# STUDNA.net
KiCad netlist of a schematic drawn in EAGLE
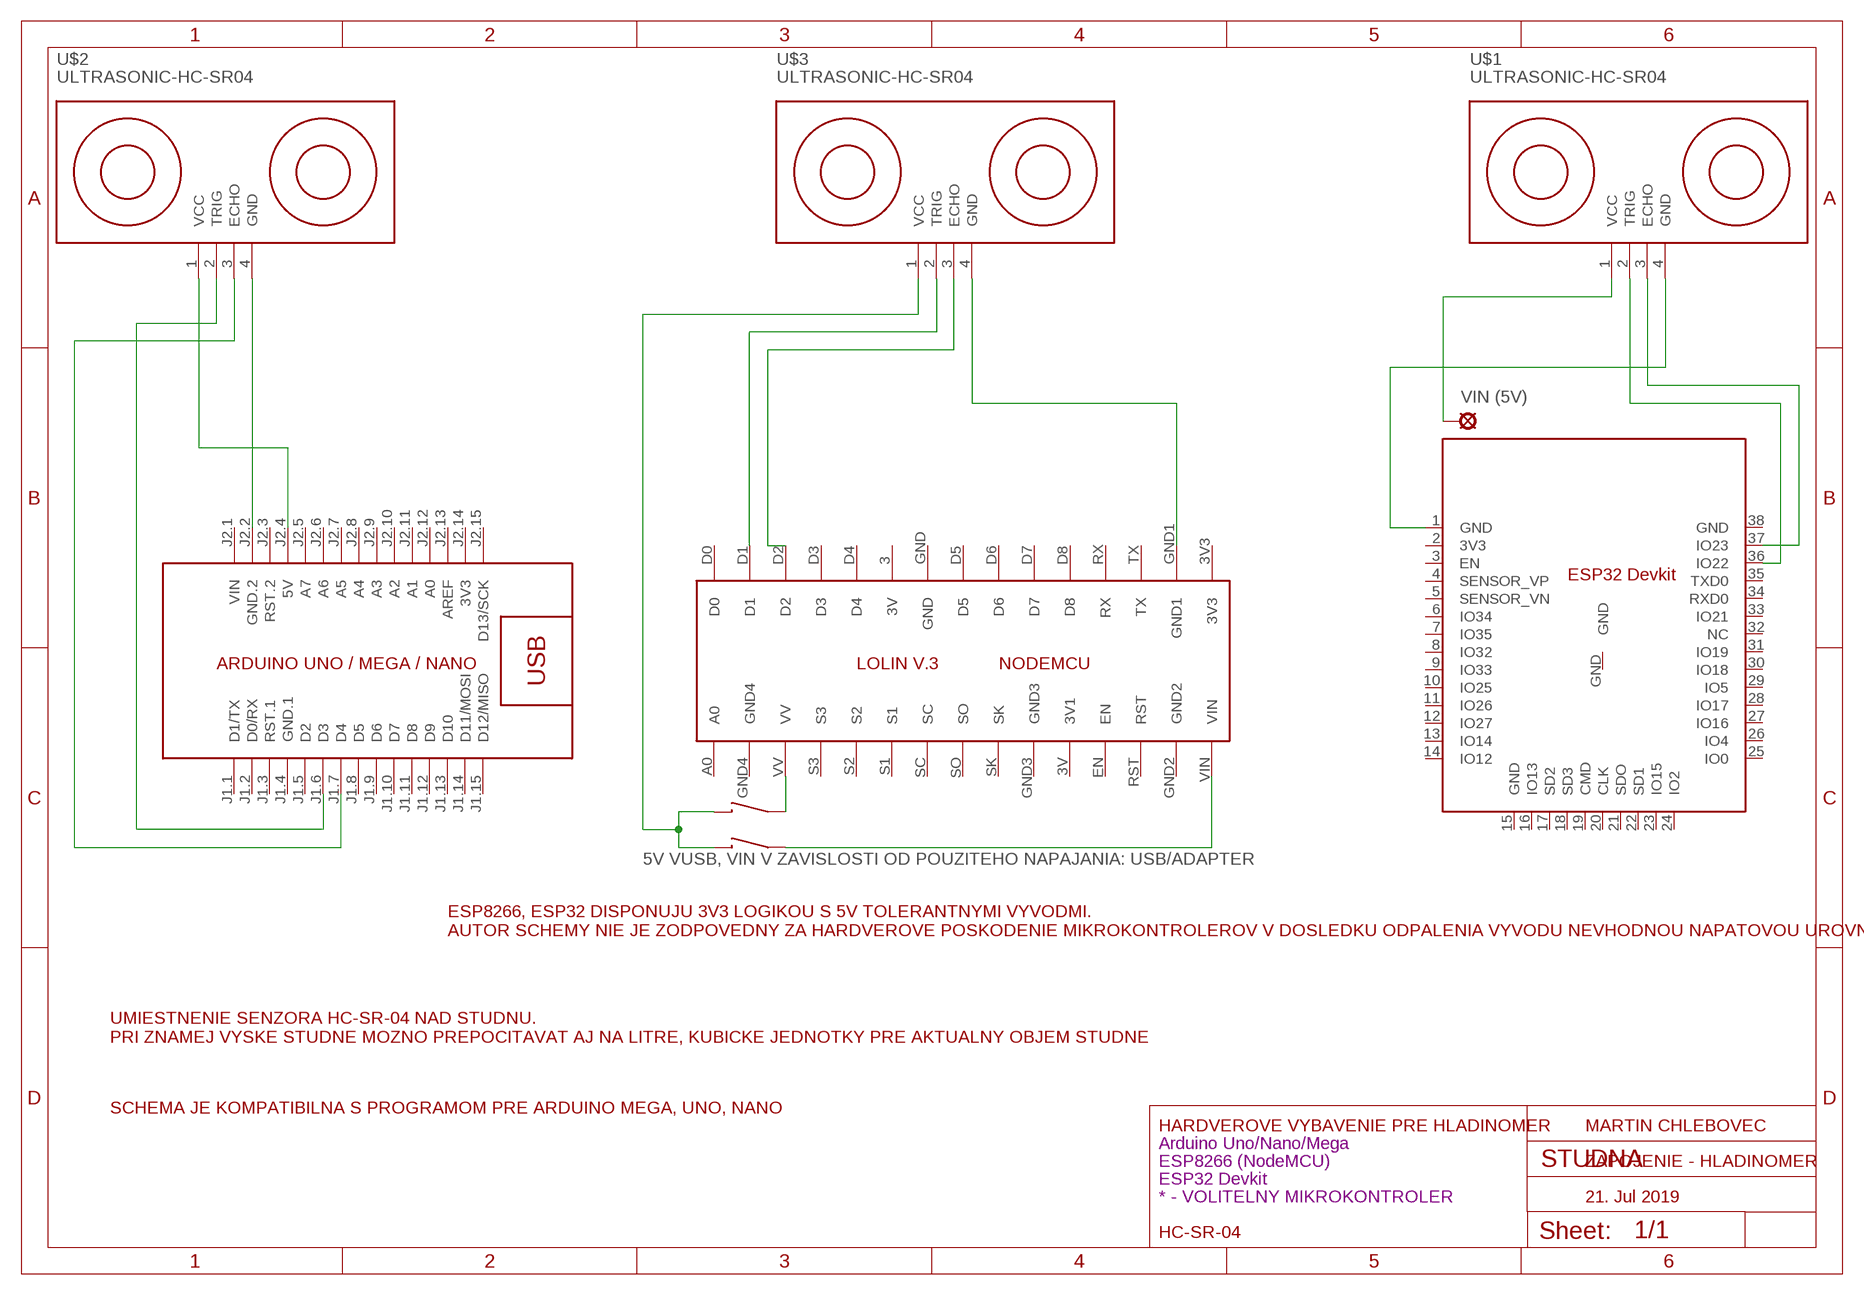
[diagram p0: schematic, sheet 1]

(export (version "E")
  (design (tool "Eeschema 10.0.6"))
  (components
    (comp (ref "A")
      (value "FINGERPAD-2B")
      (footprint "eagle-import:FINGERPAD-2B")
      (libsource (lib "eagle-import") (part "FINGERPAD-2B"))
    )
    (comp (ref "A1")
      (value "FINGERPAD-2B")
      (footprint "eagle-import:FINGERPAD-2B")
      (libsource (lib "eagle-import") (part "FINGERPAD-2B"))
    )
    (comp (ref "IC1")
      (value "LOLINV3")
      (footprint "eagle-import:LOLINV3")
      (libsource (lib "eagle-import") (part "LOLINV3"))
    )
    (comp (ref "LSP1")
      (value "MCS10B")
      (footprint "eagle-import:MCS10B")
      (libsource (lib "eagle-import") (part "MCS10B"))
    )
    (comp (ref "M1")
      (value "ARDUINO-NANO-3.0")
      (footprint "eagle-import:ARDUINO-NANO-3.0")
      (libsource (lib "eagle-import") (part "ARDUINO-NANO-3.0"))
    )
    (comp (ref "U$1")
      (value "ULTRASONIC-HC-SR04")
      (footprint "eagle-import:ULTRASONIC-HC-SR04")
      (libsource (lib "eagle-import") (part "ULTRASONIC-HC-SR04"))
    )
    (comp (ref "U$2")
      (value "ULTRASONIC-HC-SR04")
      (footprint "eagle-import:ULTRASONIC-HC-SR04")
      (libsource (lib "eagle-import") (part "ULTRASONIC-HC-SR04"))
    )
    (comp (ref "U$3")
      (value "ULTRASONIC-HC-SR04")
      (footprint "eagle-import:ULTRASONIC-HC-SR04")
      (libsource (lib "eagle-import") (part "ULTRASONIC-HC-SR04"))
    )
    (comp (ref "U1")
      (value "ESP-WROOM-32")
      (footprint "eagle-import:ESP-WROOM-32")
      (libsource (lib "eagle-import") (part "ESP-WROOM-32"))
    )
  )
  (nets
    (net (code "1") (name "/3V3") (class "Default")
      (node (ref "M1") (pin "J2.14") (pinfunction "3V3_J2.14") (pintype "power_in"))
    )
    (net (code "2") (name "/GND.1") (class "Default")
      (node (ref "M1") (pin "J1.4") (pinfunction "GND.1_J1.4") (pintype "power_in"))
    )
    (net (code "3") (name "/VIN") (class "Default")
      (node (ref "M1") (pin "J2.1") (pinfunction "VIN_J2.1") (pintype "power_in"))
    )
    (net (code "4") (name "Net-(A-Pad1)") (class "Default")
      (node (ref "A") (pin "1") (pinfunction "1_1") (pintype "passive"))
      (node (ref "IC1") (pin "VV") (pinfunction "VV_VV") (pintype "bidirectional"))
    )
    (net (code "5") (name "Net-(A1-Pad1)") (class "Default")
      (node (ref "A1") (pin "1") (pinfunction "1_1") (pintype "passive"))
      (node (ref "IC1") (pin "VIN") (pinfunction "VIN_VIN") (pintype "bidirectional"))
    )
    (net (code "6") (name "Net-(M1-5V)") (class "Default")
      (node (ref "M1") (pin "J2.4") (pinfunction "5V_J2.4") (pintype "power_in"))
      (node (ref "U$2") (pin "1") (pinfunction "VCC_1") (pintype "power_in"))
    )
    (net (code "7") (name "Net-(M1-D3)") (class "Default")
      (node (ref "M1") (pin "J1.6") (pinfunction "D3_J1.6") (pintype "bidirectional"))
      (node (ref "U$2") (pin "2") (pinfunction "TRIG_2") (pintype "input"))
    )
    (net (code "8") (name "Net-(M1-D4)") (class "Default")
      (node (ref "M1") (pin "J1.7") (pinfunction "D4_J1.7") (pintype "bidirectional"))
      (node (ref "U$2") (pin "3") (pinfunction "ECHO_3") (pintype "output"))
    )
    (net (code "9") (name "Net-(M1-GND.2)") (class "Default")
      (node (ref "M1") (pin "J2.2") (pinfunction "GND.2_J2.2") (pintype "power_in"))
      (node (ref "U$2") (pin "4") (pinfunction "GND_4") (pintype "power_in"))
    )
    (net (code "10") (name "Net-(U$1-ECHO)") (class "Default")
      (node (ref "U$1") (pin "3") (pinfunction "ECHO_3") (pintype "output"))
      (node (ref "U1") (pin "37") (pinfunction "IO23_37") (pintype "bidirectional"))
    )
    (net (code "11") (name "Net-(U$1-GND)") (class "Default")
      (node (ref "U$1") (pin "4") (pinfunction "GND_4") (pintype "power_in"))
      (node (ref "U1") (pin "1") (pinfunction "GND_1") (pintype "bidirectional"))
    )
    (net (code "12") (name "Net-(U$1-TRIG)") (class "Default")
      (node (ref "U$1") (pin "2") (pinfunction "TRIG_2") (pintype "input"))
      (node (ref "U1") (pin "36") (pinfunction "IO22_36") (pintype "bidirectional"))
    )
    (net (code "13") (name "Net-(U$1-VCC)") (class "Default")
      (node (ref "LSP1") (pin "MP") (pinfunction "MP_MP") (pintype "passive"))
      (node (ref "U$1") (pin "1") (pinfunction "VCC_1") (pintype "power_in"))
    )
    (net (code "14") (name "Net-(U$3-ECHO)") (class "Default")
      (node (ref "IC1") (pin "D2") (pinfunction "D2_D2") (pintype "bidirectional"))
      (node (ref "U$3") (pin "3") (pinfunction "ECHO_3") (pintype "output"))
    )
    (net (code "15") (name "Net-(U$3-GND)") (class "Default")
      (node (ref "IC1") (pin "GND1") (pinfunction "GND1_GND1") (pintype "bidirectional"))
      (node (ref "U$3") (pin "4") (pinfunction "GND_4") (pintype "power_in"))
    )
    (net (code "16") (name "Net-(U$3-TRIG)") (class "Default")
      (node (ref "IC1") (pin "D1") (pinfunction "D1_D1") (pintype "bidirectional"))
      (node (ref "U$3") (pin "2") (pinfunction "TRIG_2") (pintype "input"))
    )
    (net (code "17") (name "Net-(U$3-VCC)") (class "Default")
      (node (ref "A") (pin "2") (pinfunction "2_2") (pintype "passive"))
      (node (ref "A1") (pin "2") (pinfunction "2_2") (pintype "passive"))
      (node (ref "U$3") (pin "1") (pinfunction "VCC_1") (pintype "power_in"))
    )
    (net (code "18") (name "unconnected-(IC1-3V-Pad3)") (class "Default")
      (node (ref "IC1") (pin "3") (pinfunction "3V_3") (pintype "bidirectional"))
    )
    (net (code "19") (name "unconnected-(IC1-3V1-Pad3V)") (class "Default")
      (node (ref "IC1") (pin "3V") (pinfunction "3V1_3V") (pintype "bidirectional"))
    )
    (net (code "20") (name "unconnected-(IC1-Pad3V3)") (class "Default")
      (node (ref "IC1") (pin "3V3") (pinfunction "3V3_3V3") (pintype "bidirectional"))
    )
    (net (code "21") (name "unconnected-(IC1-PadA0)") (class "Default")
      (node (ref "IC1") (pin "A0") (pinfunction "A0_A0") (pintype "bidirectional"))
    )
    (net (code "22") (name "unconnected-(IC1-PadD0)") (class "Default")
      (node (ref "IC1") (pin "D0") (pinfunction "D0_D0") (pintype "bidirectional"))
    )
    (net (code "23") (name "unconnected-(IC1-PadD3)") (class "Default")
      (node (ref "IC1") (pin "D3") (pinfunction "D3_D3") (pintype "bidirectional"))
    )
    (net (code "24") (name "unconnected-(IC1-PadD4)") (class "Default")
      (node (ref "IC1") (pin "D4") (pinfunction "D4_D4") (pintype "bidirectional"))
    )
    (net (code "25") (name "unconnected-(IC1-PadD5)") (class "Default")
      (node (ref "IC1") (pin "D5") (pinfunction "D5_D5") (pintype "bidirectional"))
    )
    (net (code "26") (name "unconnected-(IC1-PadD6)") (class "Default")
      (node (ref "IC1") (pin "D6") (pinfunction "D6_D6") (pintype "bidirectional"))
    )
    (net (code "27") (name "unconnected-(IC1-PadD7)") (class "Default")
      (node (ref "IC1") (pin "D7") (pinfunction "D7_D7") (pintype "bidirectional"))
    )
    (net (code "28") (name "unconnected-(IC1-PadD8)") (class "Default")
      (node (ref "IC1") (pin "D8") (pinfunction "D8_D8") (pintype "bidirectional"))
    )
    (net (code "29") (name "unconnected-(IC1-PadEN)") (class "Default")
      (node (ref "IC1") (pin "EN") (pinfunction "EN_EN") (pintype "bidirectional"))
    )
    (net (code "30") (name "unconnected-(IC1-PadGND)") (class "Default")
      (node (ref "IC1") (pin "GND") (pinfunction "GND_GND") (pintype "bidirectional"))
    )
    (net (code "31") (name "unconnected-(IC1-PadGND2)") (class "Default")
      (node (ref "IC1") (pin "GND2") (pinfunction "GND2_GND2") (pintype "bidirectional"))
    )
    (net (code "32") (name "unconnected-(IC1-PadGND3)") (class "Default")
      (node (ref "IC1") (pin "GND3") (pinfunction "GND3_GND3") (pintype "bidirectional"))
    )
    (net (code "33") (name "unconnected-(IC1-PadGND4)") (class "Default")
      (node (ref "IC1") (pin "GND4") (pinfunction "GND4_GND4") (pintype "bidirectional"))
    )
    (net (code "34") (name "unconnected-(IC1-PadRST)") (class "Default")
      (node (ref "IC1") (pin "RST") (pinfunction "RST_RST") (pintype "bidirectional"))
    )
    (net (code "35") (name "unconnected-(IC1-PadRX)") (class "Default")
      (node (ref "IC1") (pin "RX") (pinfunction "RX_RX") (pintype "bidirectional"))
    )
    (net (code "36") (name "unconnected-(IC1-PadS1)") (class "Default")
      (node (ref "IC1") (pin "S1") (pinfunction "S1_S1") (pintype "bidirectional"))
    )
    (net (code "37") (name "unconnected-(IC1-PadS2)") (class "Default")
      (node (ref "IC1") (pin "S2") (pinfunction "S2_S2") (pintype "bidirectional"))
    )
    (net (code "38") (name "unconnected-(IC1-PadS3)") (class "Default")
      (node (ref "IC1") (pin "S3") (pinfunction "S3_S3") (pintype "bidirectional"))
    )
    (net (code "39") (name "unconnected-(IC1-PadSC)") (class "Default")
      (node (ref "IC1") (pin "SC") (pinfunction "SC_SC") (pintype "bidirectional"))
    )
    (net (code "40") (name "unconnected-(IC1-PadSK)") (class "Default")
      (node (ref "IC1") (pin "SK") (pinfunction "SK_SK") (pintype "bidirectional"))
    )
    (net (code "41") (name "unconnected-(IC1-PadSO)") (class "Default")
      (node (ref "IC1") (pin "SO") (pinfunction "SO_SO") (pintype "bidirectional"))
    )
    (net (code "42") (name "unconnected-(IC1-PadTX)") (class "Default")
      (node (ref "IC1") (pin "TX") (pinfunction "TX_TX") (pintype "bidirectional"))
    )
    (net (code "43") (name "unconnected-(M1-A0-PadJ2.12)") (class "Default")
      (node (ref "M1") (pin "J2.12") (pinfunction "A0_J2.12") (pintype "bidirectional"))
    )
    (net (code "44") (name "unconnected-(M1-A1-PadJ2.11)") (class "Default")
      (node (ref "M1") (pin "J2.11") (pinfunction "A1_J2.11") (pintype "bidirectional"))
    )
    (net (code "45") (name "unconnected-(M1-A2-PadJ2.10)") (class "Default")
      (node (ref "M1") (pin "J2.10") (pinfunction "A2_J2.10") (pintype "bidirectional"))
    )
    (net (code "46") (name "unconnected-(M1-A3-PadJ2.9)") (class "Default")
      (node (ref "M1") (pin "J2.9") (pinfunction "A3_J2.9") (pintype "bidirectional"))
    )
    (net (code "47") (name "unconnected-(M1-A4-PadJ2.8)") (class "Default")
      (node (ref "M1") (pin "J2.8") (pinfunction "A4_J2.8") (pintype "bidirectional"))
    )
    (net (code "48") (name "unconnected-(M1-A5-PadJ2.7)") (class "Default")
      (node (ref "M1") (pin "J2.7") (pinfunction "A5_J2.7") (pintype "bidirectional"))
    )
    (net (code "49") (name "unconnected-(M1-A6-PadJ2.6)") (class "Default")
      (node (ref "M1") (pin "J2.6") (pinfunction "A6_J2.6") (pintype "bidirectional"))
    )
    (net (code "50") (name "unconnected-(M1-A7-PadJ2.5)") (class "Default")
      (node (ref "M1") (pin "J2.5") (pinfunction "A7_J2.5") (pintype "bidirectional"))
    )
    (net (code "51") (name "unconnected-(M1-AREF-PadJ2.13)") (class "Default")
      (node (ref "M1") (pin "J2.13") (pinfunction "AREF_J2.13") (pintype "bidirectional"))
    )
    (net (code "52") (name "unconnected-(M1-D0{slash}RX-PadJ1.2)") (class "Default")
      (node (ref "M1") (pin "J1.2") (pinfunction "D0/RX_J1.2") (pintype "bidirectional"))
    )
    (net (code "53") (name "unconnected-(M1-D1{slash}TX-PadJ1.1)") (class "Default")
      (node (ref "M1") (pin "J1.1") (pinfunction "D1/TX_J1.1") (pintype "bidirectional"))
    )
    (net (code "54") (name "unconnected-(M1-D2-PadJ1.5)") (class "Default")
      (node (ref "M1") (pin "J1.5") (pinfunction "D2_J1.5") (pintype "bidirectional"))
    )
    (net (code "55") (name "unconnected-(M1-D5-PadJ1.8)") (class "Default")
      (node (ref "M1") (pin "J1.8") (pinfunction "D5_J1.8") (pintype "bidirectional"))
    )
    (net (code "56") (name "unconnected-(M1-D6-PadJ1.9)") (class "Default")
      (node (ref "M1") (pin "J1.9") (pinfunction "D6_J1.9") (pintype "bidirectional"))
    )
    (net (code "57") (name "unconnected-(M1-D7-PadJ1.10)") (class "Default")
      (node (ref "M1") (pin "J1.10") (pinfunction "D7_J1.10") (pintype "bidirectional"))
    )
    (net (code "58") (name "unconnected-(M1-D8-PadJ1.11)") (class "Default")
      (node (ref "M1") (pin "J1.11") (pinfunction "D8_J1.11") (pintype "bidirectional"))
    )
    (net (code "59") (name "unconnected-(M1-D9-PadJ1.12)") (class "Default")
      (node (ref "M1") (pin "J1.12") (pinfunction "D9_J1.12") (pintype "bidirectional"))
    )
    (net (code "60") (name "unconnected-(M1-D10-PadJ1.13)") (class "Default")
      (node (ref "M1") (pin "J1.13") (pinfunction "D10_J1.13") (pintype "bidirectional"))
    )
    (net (code "61") (name "unconnected-(M1-D11{slash}MOSI-PadJ1.14)") (class "Default")
      (node (ref "M1") (pin "J1.14") (pinfunction "D11/MOSI_J1.14") (pintype "bidirectional"))
    )
    (net (code "62") (name "unconnected-(M1-D12{slash}MISO-PadJ1.15)") (class "Default")
      (node (ref "M1") (pin "J1.15") (pinfunction "D12/MISO_J1.15") (pintype "bidirectional"))
    )
    (net (code "63") (name "unconnected-(M1-D13{slash}SCK-PadJ2.15)") (class "Default")
      (node (ref "M1") (pin "J2.15") (pinfunction "D13/SCK_J2.15") (pintype "bidirectional"))
    )
    (net (code "64") (name "unconnected-(M1-RST.1-PadJ1.3)") (class "Default")
      (node (ref "M1") (pin "J1.3") (pinfunction "RST.1_J1.3") (pintype "bidirectional"))
    )
    (net (code "65") (name "unconnected-(M1-RST.2-PadJ2.3)") (class "Default")
      (node (ref "M1") (pin "J2.3") (pinfunction "RST.2_J2.3") (pintype "bidirectional"))
    )
    (net (code "66") (name "unconnected-(U1-3V3-Pad2)") (class "Default")
      (node (ref "U1") (pin "2") (pinfunction "3V3_2") (pintype "bidirectional"))
    )
    (net (code "67") (name "unconnected-(U1-CLK-Pad20)") (class "Default")
      (node (ref "U1") (pin "20") (pinfunction "CLK_20") (pintype "bidirectional"))
    )
    (net (code "68") (name "unconnected-(U1-CMD-Pad19)") (class "Default")
      (node (ref "U1") (pin "19") (pinfunction "CMD_19") (pintype "bidirectional"))
    )
    (net (code "69") (name "unconnected-(U1-EN-Pad3)") (class "Default")
      (node (ref "U1") (pin "3") (pinfunction "EN_3") (pintype "bidirectional"))
    )
    (net (code "70") (name "unconnected-(U1-GND-Pad15)") (class "Default")
      (node (ref "U1") (pin "15") (pinfunction "GND_15") (pintype "bidirectional"))
    )
    (net (code "71") (name "unconnected-(U1-GND-Pad38)") (class "Default")
      (node (ref "U1") (pin "38") (pinfunction "GND_38") (pintype "bidirectional"))
    )
    (net (code "72") (name "unconnected-(U1-IO0-Pad25)") (class "Default")
      (node (ref "U1") (pin "25") (pinfunction "IO0_25") (pintype "bidirectional"))
    )
    (net (code "73") (name "unconnected-(U1-IO2-Pad24)") (class "Default")
      (node (ref "U1") (pin "24") (pinfunction "IO2_24") (pintype "bidirectional"))
    )
    (net (code "74") (name "unconnected-(U1-IO4-Pad26)") (class "Default")
      (node (ref "U1") (pin "26") (pinfunction "IO4_26") (pintype "bidirectional"))
    )
    (net (code "75") (name "unconnected-(U1-IO5-Pad29)") (class "Default")
      (node (ref "U1") (pin "29") (pinfunction "IO5_29") (pintype "bidirectional"))
    )
    (net (code "76") (name "unconnected-(U1-IO12-Pad14)") (class "Default")
      (node (ref "U1") (pin "14") (pinfunction "IO12_14") (pintype "bidirectional"))
    )
    (net (code "77") (name "unconnected-(U1-IO13-Pad16)") (class "Default")
      (node (ref "U1") (pin "16") (pinfunction "IO13_16") (pintype "bidirectional"))
    )
    (net (code "78") (name "unconnected-(U1-IO14-Pad13)") (class "Default")
      (node (ref "U1") (pin "13") (pinfunction "IO14_13") (pintype "bidirectional"))
    )
    (net (code "79") (name "unconnected-(U1-IO15-Pad23)") (class "Default")
      (node (ref "U1") (pin "23") (pinfunction "IO15_23") (pintype "bidirectional"))
    )
    (net (code "80") (name "unconnected-(U1-IO16-Pad27)") (class "Default")
      (node (ref "U1") (pin "27") (pinfunction "IO16_27") (pintype "bidirectional"))
    )
    (net (code "81") (name "unconnected-(U1-IO17-Pad28)") (class "Default")
      (node (ref "U1") (pin "28") (pinfunction "IO17_28") (pintype "bidirectional"))
    )
    (net (code "82") (name "unconnected-(U1-IO18-Pad30)") (class "Default")
      (node (ref "U1") (pin "30") (pinfunction "IO18_30") (pintype "bidirectional"))
    )
    (net (code "83") (name "unconnected-(U1-IO19-Pad31)") (class "Default")
      (node (ref "U1") (pin "31") (pinfunction "IO19_31") (pintype "bidirectional"))
    )
    (net (code "84") (name "unconnected-(U1-IO21-Pad33)") (class "Default")
      (node (ref "U1") (pin "33") (pinfunction "IO21_33") (pintype "bidirectional"))
    )
    (net (code "85") (name "unconnected-(U1-IO25-Pad10)") (class "Default")
      (node (ref "U1") (pin "10") (pinfunction "IO25_10") (pintype "bidirectional"))
    )
    (net (code "86") (name "unconnected-(U1-IO26-Pad11)") (class "Default")
      (node (ref "U1") (pin "11") (pinfunction "IO26_11") (pintype "bidirectional"))
    )
    (net (code "87") (name "unconnected-(U1-IO27-Pad12)") (class "Default")
      (node (ref "U1") (pin "12") (pinfunction "IO27_12") (pintype "bidirectional"))
    )
    (net (code "88") (name "unconnected-(U1-IO32-Pad8)") (class "Default")
      (node (ref "U1") (pin "8") (pinfunction "IO32_8") (pintype "bidirectional"))
    )
    (net (code "89") (name "unconnected-(U1-IO33-Pad9)") (class "Default")
      (node (ref "U1") (pin "9") (pinfunction "IO33_9") (pintype "bidirectional"))
    )
    (net (code "90") (name "unconnected-(U1-IO34-Pad6)") (class "Default")
      (node (ref "U1") (pin "6") (pinfunction "IO34_6") (pintype "bidirectional"))
    )
    (net (code "91") (name "unconnected-(U1-IO35-Pad7)") (class "Default")
      (node (ref "U1") (pin "7") (pinfunction "IO35_7") (pintype "bidirectional"))
    )
    (net (code "92") (name "unconnected-(U1-NC-Pad32)") (class "Default")
      (node (ref "U1") (pin "32") (pinfunction "NC_32") (pintype "bidirectional"))
    )
    (net (code "93") (name "unconnected-(U1-PadGND)") (class "Default")
      (node (ref "U1") (pin "GND") (pinfunction "GND_GND") (pintype "bidirectional"))
    )
    (net (code "94") (name "unconnected-(U1-RXD0-Pad34)") (class "Default")
      (node (ref "U1") (pin "34") (pinfunction "RXD0_34") (pintype "bidirectional"))
    )
    (net (code "95") (name "unconnected-(U1-SD1-Pad22)") (class "Default")
      (node (ref "U1") (pin "22") (pinfunction "SD1_22") (pintype "bidirectional"))
    )
    (net (code "96") (name "unconnected-(U1-SD2-Pad17)") (class "Default")
      (node (ref "U1") (pin "17") (pinfunction "SD2_17") (pintype "bidirectional"))
    )
    (net (code "97") (name "unconnected-(U1-SD3-Pad18)") (class "Default")
      (node (ref "U1") (pin "18") (pinfunction "SD3_18") (pintype "bidirectional"))
    )
    (net (code "98") (name "unconnected-(U1-SDO-Pad21)") (class "Default")
      (node (ref "U1") (pin "21") (pinfunction "SDO_21") (pintype "bidirectional"))
    )
    (net (code "99") (name "unconnected-(U1-SENSOR_VN-Pad5)") (class "Default")
      (node (ref "U1") (pin "5") (pinfunction "SENSOR_VN_5") (pintype "bidirectional"))
    )
    (net (code "100") (name "unconnected-(U1-SENSOR_VP-Pad4)") (class "Default")
      (node (ref "U1") (pin "4") (pinfunction "SENSOR_VP_4") (pintype "bidirectional"))
    )
    (net (code "101") (name "unconnected-(U1-TXD0-Pad35)") (class "Default")
      (node (ref "U1") (pin "35") (pinfunction "TXD0_35") (pintype "bidirectional"))
    )
  )
)
